# controller.net
KiCad netlist of a schematic drawn in EAGLE
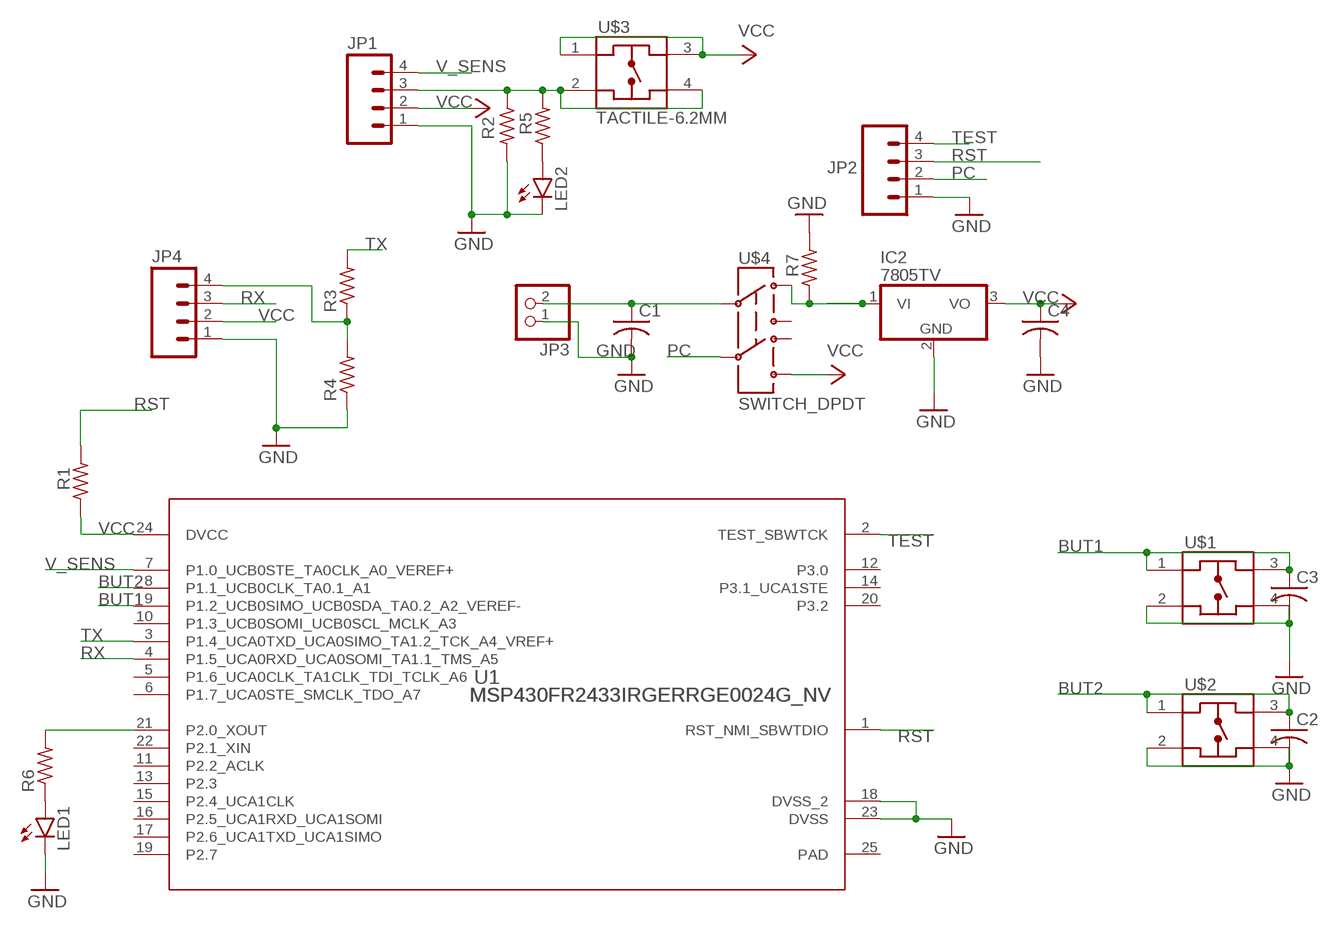
[diagram p0: schematic, sheet 1]

(export (version "E")
  (design (tool "Eeschema 10.0.6"))
  (components
    (comp (ref "C1")
      (value "C-USC1206")
      (footprint "eagle-import:C1206")
      (libsource (lib "eagle-import") (part "C-USC1206"))
    )
    (comp (ref "C2")
      (value "C-USC0603")
      (footprint "eagle-import:C0603")
      (libsource (lib "eagle-import") (part "C-USC0603"))
    )
    (comp (ref "C3")
      (value "C-USC0603")
      (footprint "eagle-import:C0603")
      (libsource (lib "eagle-import") (part "C-USC0603"))
    )
    (comp (ref "C4")
      (value "C-USC1206")
      (footprint "eagle-import:C1206")
      (libsource (lib "eagle-import") (part "C-USC1206"))
    )
    (comp (ref "IC2")
      (value "7805TV")
      (footprint "eagle-import:TO220V")
      (libsource (lib "eagle-import") (part "78TV05"))
    )
    (comp (ref "JP1")
      (value "HEADER_1X04LOCK")
      (footprint "eagle-import:1X04_LOCK")
      (libsource (lib "eagle-import") (part "HEADER_1X04LOCK"))
    )
    (comp (ref "JP2")
      (value "HEADER_1X04LOCK")
      (footprint "eagle-import:1X04_LOCK")
      (libsource (lib "eagle-import") (part "HEADER_1X04LOCK"))
    )
    (comp (ref "JP3")
      (value "PINHD-1X2")
      (footprint "eagle-import:1X02")
      (libsource (lib "eagle-import") (part "PINHD-1X2"))
    )
    (comp (ref "JP4")
      (value "HEADER_1X04LOCK")
      (footprint "eagle-import:1X04_LOCK")
      (libsource (lib "eagle-import") (part "HEADER_1X04LOCK"))
    )
    (comp (ref "LED1")
      (value "LED5MM")
      (footprint "eagle-import:LED5MM")
      (libsource (lib "eagle-import") (part "LED5MM"))
    )
    (comp (ref "LED2")
      (value "LED5MM")
      (footprint "eagle-import:LED5MM")
      (libsource (lib "eagle-import") (part "LED5MM"))
    )
    (comp (ref "R1")
      (value "R-US_R1206")
      (footprint "eagle-import:R1206")
      (libsource (lib "eagle-import") (part "R-US_R1206"))
    )
    (comp (ref "R2")
      (value "R-US_R1206")
      (footprint "eagle-import:R1206")
      (libsource (lib "eagle-import") (part "R-US_R1206"))
    )
    (comp (ref "R3")
      (value "R-US_R1206")
      (footprint "eagle-import:R1206")
      (libsource (lib "eagle-import") (part "R-US_R1206"))
    )
    (comp (ref "R4")
      (value "R-US_R1206")
      (footprint "eagle-import:R1206")
      (libsource (lib "eagle-import") (part "R-US_R1206"))
    )
    (comp (ref "R5")
      (value "R-US_R1206")
      (footprint "eagle-import:R1206")
      (libsource (lib "eagle-import") (part "R-US_R1206"))
    )
    (comp (ref "R6")
      (value "R-US_R1206")
      (footprint "eagle-import:R1206")
      (libsource (lib "eagle-import") (part "R-US_R1206"))
    )
    (comp (ref "R7")
      (value "R-US_R1206")
      (footprint "eagle-import:R1206")
      (libsource (lib "eagle-import") (part "R-US_R1206"))
    )
    (comp (ref "U$1")
      (value "TACTILE-6.2MM")
      (footprint "eagle-import:222_AM")
      (libsource (lib "eagle-import") (part "TACTILE-6.2MM"))
    )
    (comp (ref "U$2")
      (value "TACTILE-6.2MM")
      (footprint "eagle-import:222_AM")
      (libsource (lib "eagle-import") (part "TACTILE-6.2MM"))
    )
    (comp (ref "U$3")
      (value "TACTILE-6.2MM")
      (footprint "eagle-import:222_AM")
      (libsource (lib "eagle-import") (part "TACTILE-6.2MM"))
    )
    (comp (ref "U$4")
      (value "SWITCH_DPDT")
      (footprint "eagle-import:JS_DPDT_TH")
      (libsource (lib "eagle-import") (part "SWITCH_DPDT"))
    )
    (comp (ref "U1")
      (value "MSP430FR2433IRGERRGE0024G_NV")
      (footprint "eagle-import:RGE0024G_NV")
      (fields
        (field (name "MANUFACTURER_PART_NUMBER") "MSP430FR2433IRGER")
        (field (name "COPYRIGHT") "Copyright (C) 2023 Ultra Librarian. All rights reserved.")
      )
      (libsource (lib "eagle-import") (part "MSP430FR2433IRGERRGE0024G_NV"))
    )
  )
  (nets
    (net (code "1") (name "/BUT1") (class "Default")
      (node (ref "C3") (pin "1") (pinfunction "1_1") (pintype "passive"))
      (node (ref "U$1") (pin "1") (pinfunction "1_1") (pintype "passive"))
      (node (ref "U$1") (pin "3") (pinfunction "3_3") (pintype "passive"))
      (node (ref "U1") (pin "9") (pinfunction "P1.2_UCB0SIMO_UCB0SDA_TA0.2_A2_VEREF-_9") (pintype "bidirectional"))
    )
    (net (code "2") (name "/BUT2") (class "Default")
      (node (ref "C2") (pin "1") (pinfunction "1_1") (pintype "passive"))
      (node (ref "U$2") (pin "1") (pinfunction "1_1") (pintype "passive"))
      (node (ref "U$2") (pin "3") (pinfunction "3_3") (pintype "passive"))
      (node (ref "U1") (pin "8") (pinfunction "P1.1_UCB0CLK_TA0.1_A1_8") (pintype "bidirectional"))
    )
    (net (code "3") (name "/PAD") (class "Default")
      (node (ref "U1") (pin "25") (pinfunction "PAD_25") (pintype "power_in"))
    )
    (net (code "4") (name "/PC") (class "Default")
      (node (ref "JP2") (pin "2") (pinfunction "2_2") (pintype "passive"))
      (node (ref "U$4") (pin "5") (pinfunction "5_5") (pintype "bidirectional"))
    )
    (net (code "5") (name "/RST") (class "Default")
      (node (ref "JP2") (pin "3") (pinfunction "3_3") (pintype "passive"))
      (node (ref "R1") (pin "2") (pinfunction "2_2") (pintype "passive"))
      (node (ref "U1") (pin "1") (pinfunction "RST_NMI_SBWTDIO_1") (pintype "bidirectional"))
    )
    (net (code "6") (name "/RX") (class "Default")
      (node (ref "JP4") (pin "3") (pinfunction "3_3") (pintype "passive"))
      (node (ref "U1") (pin "4") (pinfunction "P1.5_UCA0RXD_UCA0SOMI_TA1.1_TMS_A5_4") (pintype "bidirectional"))
    )
    (net (code "7") (name "/TEST") (class "Default")
      (node (ref "JP2") (pin "4") (pinfunction "4_4") (pintype "passive"))
      (node (ref "U1") (pin "2") (pinfunction "TEST_SBWTCK_2") (pintype "input"))
    )
    (net (code "8") (name "/TX") (class "Default")
      (node (ref "R3") (pin "2") (pinfunction "2_2") (pintype "passive"))
      (node (ref "U1") (pin "3") (pinfunction "P1.4_UCA0TXD_UCA0SIMO_TA1.2_TCK_A4_VREF+_3") (pintype "bidirectional"))
    )
    (net (code "9") (name "/V_SENS") (class "Default")
      (node (ref "JP1") (pin "4") (pinfunction "4_4") (pintype "passive"))
      (node (ref "U1") (pin "7") (pinfunction "P1.0_UCB0STE_TA0CLK_A0_VEREF+_7") (pintype "bidirectional"))
    )
    (net (code "10") (name "GND") (class "Default")
      (node (ref "C1") (pin "2") (pinfunction "2_2") (pintype "passive"))
      (node (ref "C2") (pin "2") (pinfunction "2_2") (pintype "passive"))
      (node (ref "C3") (pin "2") (pinfunction "2_2") (pintype "passive"))
      (node (ref "C4") (pin "2") (pinfunction "2_2") (pintype "passive"))
      (node (ref "IC2") (pin "2") (pinfunction "GND_2") (pintype "passive"))
      (node (ref "JP1") (pin "1") (pinfunction "1_1") (pintype "passive"))
      (node (ref "JP2") (pin "1") (pinfunction "1_1") (pintype "passive"))
      (node (ref "JP3") (pin "1") (pinfunction "1_1") (pintype "passive"))
      (node (ref "JP4") (pin "1") (pinfunction "1_1") (pintype "passive"))
      (node (ref "LED1") (pin "K") (pinfunction "C_K") (pintype "passive"))
      (node (ref "LED2") (pin "K") (pinfunction "C_K") (pintype "passive"))
      (node (ref "R2") (pin "2") (pinfunction "2_2") (pintype "passive"))
      (node (ref "R4") (pin "1") (pinfunction "1_1") (pintype "passive"))
      (node (ref "R7") (pin "2") (pinfunction "2_2") (pintype "passive"))
      (node (ref "U$1") (pin "2") (pinfunction "2_2") (pintype "passive"))
      (node (ref "U$1") (pin "4") (pinfunction "4_4") (pintype "passive"))
      (node (ref "U$2") (pin "2") (pinfunction "2_2") (pintype "passive"))
      (node (ref "U$2") (pin "4") (pinfunction "4_4") (pintype "passive"))
      (node (ref "U1") (pin "18") (pinfunction "DVSS_2_18") (pintype "power_in"))
      (node (ref "U1") (pin "23") (pinfunction "DVSS_23") (pintype "power_in"))
    )
    (net (code "11") (name "Net-(C1-Pad1)") (class "Default")
      (node (ref "C1") (pin "1") (pinfunction "1_1") (pintype "passive"))
      (node (ref "JP3") (pin "2") (pinfunction "2_2") (pintype "passive"))
      (node (ref "U$4") (pin "2") (pinfunction "2_2") (pintype "bidirectional"))
    )
    (net (code "12") (name "Net-(IC2-VI)") (class "Default")
      (node (ref "IC2") (pin "1") (pinfunction "VI_1") (pintype "input"))
      (node (ref "R7") (pin "1") (pinfunction "1_1") (pintype "passive"))
      (node (ref "U$4") (pin "1") (pinfunction "1_1") (pintype "bidirectional"))
    )
    (net (code "13") (name "Net-(JP1-Pad3)") (class "Default")
      (node (ref "JP1") (pin "3") (pinfunction "3_3") (pintype "passive"))
      (node (ref "R2") (pin "1") (pinfunction "1_1") (pintype "passive"))
      (node (ref "R5") (pin "2") (pinfunction "2_2") (pintype "passive"))
      (node (ref "U$3") (pin "2") (pinfunction "2_2") (pintype "passive"))
      (node (ref "U$3") (pin "4") (pinfunction "4_4") (pintype "passive"))
    )
    (net (code "14") (name "Net-(JP4-Pad4)") (class "Default")
      (node (ref "JP4") (pin "4") (pinfunction "4_4") (pintype "passive"))
      (node (ref "R3") (pin "1") (pinfunction "1_1") (pintype "passive"))
      (node (ref "R4") (pin "2") (pinfunction "2_2") (pintype "passive"))
    )
    (net (code "15") (name "Net-(LED1-PadA)") (class "Default")
      (node (ref "LED1") (pin "A") (pinfunction "A_A") (pintype "passive"))
      (node (ref "R6") (pin "1") (pinfunction "1_1") (pintype "passive"))
    )
    (net (code "16") (name "Net-(LED2-PadA)") (class "Default")
      (node (ref "LED2") (pin "A") (pinfunction "A_A") (pintype "passive"))
      (node (ref "R5") (pin "1") (pinfunction "1_1") (pintype "passive"))
    )
    (net (code "17") (name "Net-(U1-P2.0_XOUT)") (class "Default")
      (node (ref "R6") (pin "2") (pinfunction "2_2") (pintype "passive"))
      (node (ref "U1") (pin "21") (pinfunction "P2.0_XOUT_21") (pintype "bidirectional"))
    )
    (net (code "18") (name "VCC") (class "Default")
      (node (ref "C4") (pin "1") (pinfunction "1_1") (pintype "passive"))
      (node (ref "IC2") (pin "3") (pinfunction "VO_3") (pintype "passive"))
      (node (ref "JP1") (pin "2") (pinfunction "2_2") (pintype "passive"))
      (node (ref "JP4") (pin "2") (pinfunction "2_2") (pintype "passive"))
      (node (ref "R1") (pin "1") (pinfunction "1_1") (pintype "passive"))
      (node (ref "U$3") (pin "1") (pinfunction "1_1") (pintype "passive"))
      (node (ref "U$3") (pin "3") (pinfunction "3_3") (pintype "passive"))
      (node (ref "U$4") (pin "6") (pinfunction "6_6") (pintype "bidirectional"))
      (node (ref "U1") (pin "24") (pinfunction "DVCC_24") (pintype "power_in"))
    )
    (net (code "19") (name "unconnected-(U$4-Pad3)") (class "Default")
      (node (ref "U$4") (pin "3") (pinfunction "3_3") (pintype "bidirectional"))
    )
    (net (code "20") (name "unconnected-(U$4-Pad4)") (class "Default")
      (node (ref "U$4") (pin "4") (pinfunction "4_4") (pintype "bidirectional"))
    )
    (net (code "21") (name "unconnected-(U1-P1.3_UCB0SOMI_UCB0SCL_MCLK_A3-Pad10)") (class "Default")
      (node (ref "U1") (pin "10") (pinfunction "P1.3_UCB0SOMI_UCB0SCL_MCLK_A3_10") (pintype "bidirectional"))
    )
    (net (code "22") (name "unconnected-(U1-P1.6_UCA0CLK_TA1CLK_TDI_TCLK_A6-Pad5)") (class "Default")
      (node (ref "U1") (pin "5") (pinfunction "P1.6_UCA0CLK_TA1CLK_TDI_TCLK_A6_5") (pintype "bidirectional"))
    )
    (net (code "23") (name "unconnected-(U1-P1.7_UCA0STE_SMCLK_TDO_A7-Pad6)") (class "Default")
      (node (ref "U1") (pin "6") (pinfunction "P1.7_UCA0STE_SMCLK_TDO_A7_6") (pintype "bidirectional"))
    )
    (net (code "24") (name "unconnected-(U1-P2.1_XIN-Pad22)") (class "Default")
      (node (ref "U1") (pin "22") (pinfunction "P2.1_XIN_22") (pintype "bidirectional"))
    )
    (net (code "25") (name "unconnected-(U1-P2.2_ACLK-Pad11)") (class "Default")
      (node (ref "U1") (pin "11") (pinfunction "P2.2_ACLK_11") (pintype "bidirectional"))
    )
    (net (code "26") (name "unconnected-(U1-P2.3-Pad13)") (class "Default")
      (node (ref "U1") (pin "13") (pinfunction "P2.3_13") (pintype "bidirectional"))
    )
    (net (code "27") (name "unconnected-(U1-P2.4_UCA1CLK-Pad15)") (class "Default")
      (node (ref "U1") (pin "15") (pinfunction "P2.4_UCA1CLK_15") (pintype "bidirectional"))
    )
    (net (code "28") (name "unconnected-(U1-P2.5_UCA1RXD_UCA1SOMI-Pad16)") (class "Default")
      (node (ref "U1") (pin "16") (pinfunction "P2.5_UCA1RXD_UCA1SOMI_16") (pintype "bidirectional"))
    )
    (net (code "29") (name "unconnected-(U1-P2.6_UCA1TXD_UCA1SIMO-Pad17)") (class "Default")
      (node (ref "U1") (pin "17") (pinfunction "P2.6_UCA1TXD_UCA1SIMO_17") (pintype "bidirectional"))
    )
    (net (code "30") (name "unconnected-(U1-P2.7-Pad19)") (class "Default")
      (node (ref "U1") (pin "19") (pinfunction "P2.7_19") (pintype "bidirectional"))
    )
    (net (code "31") (name "unconnected-(U1-P3.0-Pad12)") (class "Default")
      (node (ref "U1") (pin "12") (pinfunction "P3.0_12") (pintype "bidirectional"))
    )
    (net (code "32") (name "unconnected-(U1-P3.1_UCA1STE-Pad14)") (class "Default")
      (node (ref "U1") (pin "14") (pinfunction "P3.1_UCA1STE_14") (pintype "bidirectional"))
    )
    (net (code "33") (name "unconnected-(U1-P3.2-Pad20)") (class "Default")
      (node (ref "U1") (pin "20") (pinfunction "P3.2_20") (pintype "bidirectional"))
    )
  )
)
